# camera_interface.net
KiCad netlist of a schematic drawn in Altium Designer
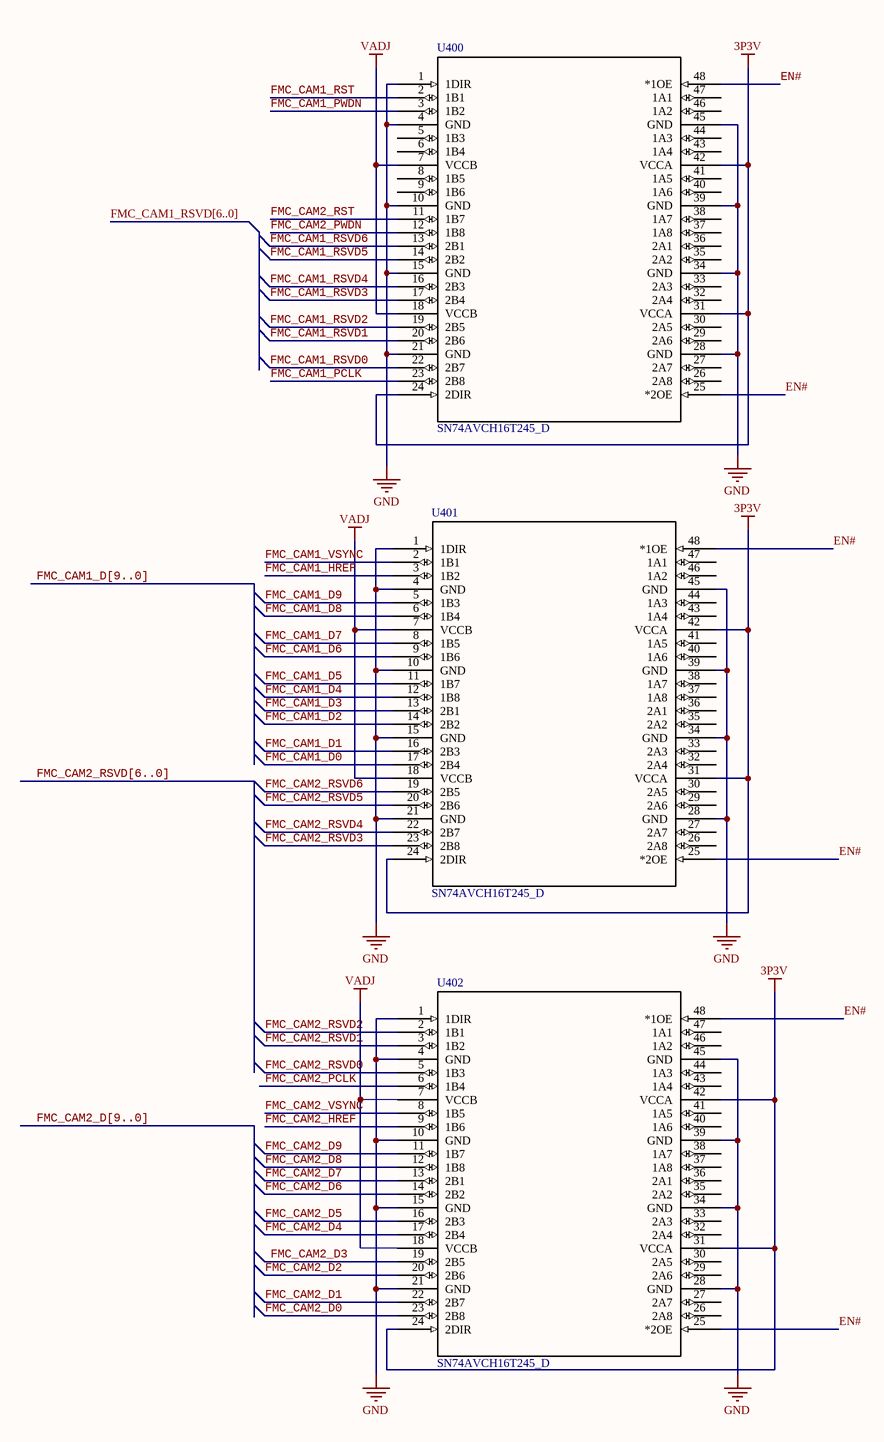
[diagram p0: camera_interface.SchDoc]

(export (version "E")
  (design (tool "Eeschema 10.0.6"))
  (components
    (comp (ref "U400")
      (value "SN74AVCH16T245_D")
      (footprint "DGV48")
      (description "Imported")
      (fields
        (field (name "MANUFACTURER") "Texas Instruments")
        (field (name "GENERIC_PART_NUMBER") "SN74AVCH16T245")
      )
      (libsource (lib "SN74AVCH16T245DGV") (part "SN74AVCH16T245_D"))
    )
    (comp (ref "U401")
      (value "SN74AVCH16T245_D")
      (footprint "DGV48")
      (description "Imported")
      (fields
        (field (name "MANUFACTURER") "Texas Instruments")
        (field (name "GENERIC_PART_NUMBER") "SN74AVCH16T245")
      )
      (libsource (lib "SN74AVCH16T245DGV") (part "SN74AVCH16T245_D"))
    )
    (comp (ref "U402")
      (value "SN74AVCH16T245_D")
      (footprint "DGV48")
      (description "Imported")
      (fields
        (field (name "MANUFACTURER") "Texas Instruments")
        (field (name "GENERIC_PART_NUMBER") "SN74AVCH16T245")
      )
      (libsource (lib "SN74AVCH16T245DGV") (part "SN74AVCH16T245_D"))
    )
  )
  (nets
    (net (code "1") (name "/EN#") (class "Default")
      (node (ref "U400") (pin "25") (pinfunction "*2OE_25") (pintype "input"))
      (node (ref "U400") (pin "48") (pinfunction "*1OE_48") (pintype "input"))
      (node (ref "U401") (pin "25") (pinfunction "*2OE_25") (pintype "input"))
      (node (ref "U401") (pin "48") (pinfunction "*1OE_48") (pintype "input"))
      (node (ref "U402") (pin "25") (pinfunction "*2OE_25") (pintype "input"))
      (node (ref "U402") (pin "48") (pinfunction "*1OE_48") (pintype "input"))
    )
    (net (code "2") (name "/FMC_CAM1_D0") (class "Default")
      (node (ref "U401") (pin "17") (pinfunction "2B4_17") (pintype "bidirectional"))
    )
    (net (code "3") (name "/FMC_CAM1_D1") (class "Default")
      (node (ref "U401") (pin "16") (pinfunction "2B3_16") (pintype "bidirectional"))
    )
    (net (code "4") (name "/FMC_CAM1_D2") (class "Default")
      (node (ref "U401") (pin "14") (pinfunction "2B2_14") (pintype "bidirectional"))
    )
    (net (code "5") (name "/FMC_CAM1_D3") (class "Default")
      (node (ref "U401") (pin "13") (pinfunction "2B1_13") (pintype "bidirectional"))
    )
    (net (code "6") (name "/FMC_CAM1_D4") (class "Default")
      (node (ref "U401") (pin "12") (pinfunction "1B8_12") (pintype "bidirectional"))
    )
    (net (code "7") (name "/FMC_CAM1_D5") (class "Default")
      (node (ref "U401") (pin "11") (pinfunction "1B7_11") (pintype "bidirectional"))
    )
    (net (code "8") (name "/FMC_CAM1_D6") (class "Default")
      (node (ref "U401") (pin "9") (pinfunction "1B6_9") (pintype "bidirectional"))
    )
    (net (code "9") (name "/FMC_CAM1_D7") (class "Default")
      (node (ref "U401") (pin "8") (pinfunction "1B5_8") (pintype "bidirectional"))
    )
    (net (code "10") (name "/FMC_CAM1_D8") (class "Default")
      (node (ref "U401") (pin "6") (pinfunction "1B4_6") (pintype "bidirectional"))
    )
    (net (code "11") (name "/FMC_CAM1_D9") (class "Default")
      (node (ref "U401") (pin "5") (pinfunction "1B3_5") (pintype "bidirectional"))
    )
    (net (code "13") (name "/FMC_CAM1_HREF") (class "Default")
      (node (ref "U401") (pin "3") (pinfunction "1B2_3") (pintype "bidirectional"))
    )
    (net (code "14") (name "/FMC_CAM1_PCLK") (class "Default")
      (node (ref "U400") (pin "23") (pinfunction "2B8_23") (pintype "bidirectional"))
    )
    (net (code "15") (name "/FMC_CAM1_PWDN") (class "Default")
      (node (ref "U400") (pin "3") (pinfunction "1B2_3") (pintype "bidirectional"))
    )
    (net (code "16") (name "/FMC_CAM1_RST") (class "Default")
      (node (ref "U400") (pin "2") (pinfunction "1B1_2") (pintype "bidirectional"))
    )
    (net (code "17") (name "/FMC_CAM1_RSVD0") (class "Default")
      (node (ref "U400") (pin "22") (pinfunction "2B7_22") (pintype "bidirectional"))
    )
    (net (code "18") (name "/FMC_CAM1_RSVD1") (class "Default")
      (node (ref "U400") (pin "20") (pinfunction "2B6_20") (pintype "bidirectional"))
    )
    (net (code "19") (name "/FMC_CAM1_RSVD2") (class "Default")
      (node (ref "U400") (pin "19") (pinfunction "2B5_19") (pintype "bidirectional"))
    )
    (net (code "20") (name "/FMC_CAM1_RSVD3") (class "Default")
      (node (ref "U400") (pin "17") (pinfunction "2B4_17") (pintype "bidirectional"))
    )
    (net (code "21") (name "/FMC_CAM1_RSVD4") (class "Default")
      (node (ref "U400") (pin "16") (pinfunction "2B3_16") (pintype "bidirectional"))
    )
    (net (code "22") (name "/FMC_CAM1_RSVD5") (class "Default")
      (node (ref "U400") (pin "14") (pinfunction "2B2_14") (pintype "bidirectional"))
    )
    (net (code "23") (name "/FMC_CAM1_RSVD6") (class "Default")
      (node (ref "U400") (pin "13") (pinfunction "2B1_13") (pintype "bidirectional"))
    )
    (net (code "25") (name "/FMC_CAM1_VSYNC") (class "Default")
      (node (ref "U401") (pin "2") (pinfunction "1B1_2") (pintype "bidirectional"))
    )
    (net (code "26") (name "/FMC_CAM2_D0") (class "Default")
      (node (ref "U402") (pin "23") (pinfunction "2B8_23") (pintype "bidirectional"))
    )
    (net (code "27") (name "/FMC_CAM2_D1") (class "Default")
      (node (ref "U402") (pin "22") (pinfunction "2B7_22") (pintype "bidirectional"))
    )
    (net (code "28") (name "/FMC_CAM2_D2") (class "Default")
      (node (ref "U402") (pin "20") (pinfunction "2B6_20") (pintype "bidirectional"))
    )
    (net (code "29") (name "/FMC_CAM2_D3") (class "Default")
      (node (ref "U402") (pin "19") (pinfunction "2B5_19") (pintype "bidirectional"))
    )
    (net (code "30") (name "/FMC_CAM2_D4") (class "Default")
      (node (ref "U402") (pin "17") (pinfunction "2B4_17") (pintype "bidirectional"))
    )
    (net (code "31") (name "/FMC_CAM2_D5") (class "Default")
      (node (ref "U402") (pin "16") (pinfunction "2B3_16") (pintype "bidirectional"))
    )
    (net (code "32") (name "/FMC_CAM2_D6") (class "Default")
      (node (ref "U402") (pin "14") (pinfunction "2B2_14") (pintype "bidirectional"))
    )
    (net (code "33") (name "/FMC_CAM2_D7") (class "Default")
      (node (ref "U402") (pin "13") (pinfunction "2B1_13") (pintype "bidirectional"))
    )
    (net (code "34") (name "/FMC_CAM2_D8") (class "Default")
      (node (ref "U402") (pin "12") (pinfunction "1B8_12") (pintype "bidirectional"))
    )
    (net (code "35") (name "/FMC_CAM2_D9") (class "Default")
      (node (ref "U402") (pin "11") (pinfunction "1B7_11") (pintype "bidirectional"))
    )
    (net (code "37") (name "/FMC_CAM2_HREF") (class "Default")
      (node (ref "U402") (pin "9") (pinfunction "1B6_9") (pintype "bidirectional"))
    )
    (net (code "38") (name "/FMC_CAM2_PCLK") (class "Default")
      (node (ref "U402") (pin "6") (pinfunction "1B4_6") (pintype "bidirectional"))
    )
    (net (code "39") (name "/FMC_CAM2_PWDN") (class "Default")
      (node (ref "U400") (pin "12") (pinfunction "1B8_12") (pintype "bidirectional"))
    )
    (net (code "40") (name "/FMC_CAM2_RST") (class "Default")
      (node (ref "U400") (pin "11") (pinfunction "1B7_11") (pintype "bidirectional"))
    )
    (net (code "41") (name "/FMC_CAM2_RSVD0") (class "Default")
      (node (ref "U402") (pin "5") (pinfunction "1B3_5") (pintype "bidirectional"))
    )
    (net (code "42") (name "/FMC_CAM2_RSVD1") (class "Default")
      (node (ref "U402") (pin "3") (pinfunction "1B2_3") (pintype "bidirectional"))
    )
    (net (code "43") (name "/FMC_CAM2_RSVD2") (class "Default")
      (node (ref "U402") (pin "2") (pinfunction "1B1_2") (pintype "bidirectional"))
    )
    (net (code "44") (name "/FMC_CAM2_RSVD3") (class "Default")
      (node (ref "U401") (pin "23") (pinfunction "2B8_23") (pintype "bidirectional"))
    )
    (net (code "45") (name "/FMC_CAM2_RSVD4") (class "Default")
      (node (ref "U401") (pin "22") (pinfunction "2B7_22") (pintype "bidirectional"))
    )
    (net (code "46") (name "/FMC_CAM2_RSVD5") (class "Default")
      (node (ref "U401") (pin "20") (pinfunction "2B6_20") (pintype "bidirectional"))
    )
    (net (code "47") (name "/FMC_CAM2_RSVD6") (class "Default")
      (node (ref "U401") (pin "19") (pinfunction "2B5_19") (pintype "bidirectional"))
    )
    (net (code "49") (name "/FMC_CAM2_VSYNC") (class "Default")
      (node (ref "U402") (pin "8") (pinfunction "1B5_8") (pintype "bidirectional"))
    )
    (net (code "50") (name "3P3V") (class "Default")
      (node (ref "U400") (pin "24") (pinfunction "2DIR_24") (pintype "input"))
      (node (ref "U400") (pin "31") (pinfunction "VCCA_31") (pintype "power_in"))
      (node (ref "U400") (pin "42") (pinfunction "VCCA_42") (pintype "power_in"))
      (node (ref "U401") (pin "24") (pinfunction "2DIR_24") (pintype "input"))
      (node (ref "U401") (pin "31") (pinfunction "VCCA_31") (pintype "power_in"))
      (node (ref "U401") (pin "42") (pinfunction "VCCA_42") (pintype "power_in"))
      (node (ref "U402") (pin "24") (pinfunction "2DIR_24") (pintype "input"))
      (node (ref "U402") (pin "31") (pinfunction "VCCA_31") (pintype "power_in"))
      (node (ref "U402") (pin "42") (pinfunction "VCCA_42") (pintype "power_in"))
    )
    (net (code "51") (name "GND") (class "Default")
      (node (ref "U400") (pin "1") (pinfunction "1DIR_1") (pintype "input"))
      (node (ref "U400") (pin "10") (pinfunction "GND_10") (pintype "power_in"))
      (node (ref "U400") (pin "15") (pinfunction "GND_15") (pintype "power_in"))
      (node (ref "U400") (pin "21") (pinfunction "GND_21") (pintype "power_in"))
      (node (ref "U400") (pin "28") (pinfunction "GND_28") (pintype "power_in"))
      (node (ref "U400") (pin "34") (pinfunction "GND_34") (pintype "power_in"))
      (node (ref "U400") (pin "39") (pinfunction "GND_39") (pintype "power_in"))
      (node (ref "U400") (pin "4") (pinfunction "GND_4") (pintype "power_in"))
      (node (ref "U400") (pin "45") (pinfunction "GND_45") (pintype "power_in"))
      (node (ref "U401") (pin "1") (pinfunction "1DIR_1") (pintype "input"))
      (node (ref "U401") (pin "10") (pinfunction "GND_10") (pintype "power_in"))
      (node (ref "U401") (pin "15") (pinfunction "GND_15") (pintype "power_in"))
      (node (ref "U401") (pin "21") (pinfunction "GND_21") (pintype "power_in"))
      (node (ref "U401") (pin "28") (pinfunction "GND_28") (pintype "power_in"))
      (node (ref "U401") (pin "34") (pinfunction "GND_34") (pintype "power_in"))
      (node (ref "U401") (pin "39") (pinfunction "GND_39") (pintype "power_in"))
      (node (ref "U401") (pin "4") (pinfunction "GND_4") (pintype "power_in"))
      (node (ref "U401") (pin "45") (pinfunction "GND_45") (pintype "power_in"))
      (node (ref "U402") (pin "1") (pinfunction "1DIR_1") (pintype "input"))
      (node (ref "U402") (pin "10") (pinfunction "GND_10") (pintype "power_in"))
      (node (ref "U402") (pin "15") (pinfunction "GND_15") (pintype "power_in"))
      (node (ref "U402") (pin "21") (pinfunction "GND_21") (pintype "power_in"))
      (node (ref "U402") (pin "28") (pinfunction "GND_28") (pintype "power_in"))
      (node (ref "U402") (pin "34") (pinfunction "GND_34") (pintype "power_in"))
      (node (ref "U402") (pin "39") (pinfunction "GND_39") (pintype "power_in"))
      (node (ref "U402") (pin "4") (pinfunction "GND_4") (pintype "power_in"))
      (node (ref "U402") (pin "45") (pinfunction "GND_45") (pintype "power_in"))
    )
    (net (code "52") (name "VADJ") (class "Default")
      (node (ref "U400") (pin "18") (pinfunction "VCCB_18") (pintype "power_in"))
      (node (ref "U400") (pin "7") (pinfunction "VCCB_7") (pintype "power_in"))
      (node (ref "U401") (pin "18") (pinfunction "VCCB_18") (pintype "power_in"))
      (node (ref "U401") (pin "7") (pinfunction "VCCB_7") (pintype "power_in"))
      (node (ref "U402") (pin "18") (pinfunction "VCCB_18") (pintype "power_in"))
      (node (ref "U402") (pin "7") (pinfunction "VCCB_7") (pintype "power_in"))
    )
    (net (code "53") (name "unconnected-(U400-1A1-Pad47)") (class "Default")
      (node (ref "U400") (pin "47") (pinfunction "1A1_47") (pintype "bidirectional"))
    )
    (net (code "54") (name "unconnected-(U400-1A2-Pad46)") (class "Default")
      (node (ref "U400") (pin "46") (pinfunction "1A2_46") (pintype "bidirectional"))
    )
    (net (code "55") (name "unconnected-(U400-1A3-Pad44)") (class "Default")
      (node (ref "U400") (pin "44") (pinfunction "1A3_44") (pintype "bidirectional"))
    )
    (net (code "56") (name "unconnected-(U400-1A4-Pad43)") (class "Default")
      (node (ref "U400") (pin "43") (pinfunction "1A4_43") (pintype "bidirectional"))
    )
    (net (code "57") (name "unconnected-(U400-1A5-Pad41)") (class "Default")
      (node (ref "U400") (pin "41") (pinfunction "1A5_41") (pintype "bidirectional"))
    )
    (net (code "58") (name "unconnected-(U400-1A6-Pad40)") (class "Default")
      (node (ref "U400") (pin "40") (pinfunction "1A6_40") (pintype "bidirectional"))
    )
    (net (code "59") (name "unconnected-(U400-1A7-Pad38)") (class "Default")
      (node (ref "U400") (pin "38") (pinfunction "1A7_38") (pintype "bidirectional"))
    )
    (net (code "60") (name "unconnected-(U400-1A8-Pad37)") (class "Default")
      (node (ref "U400") (pin "37") (pinfunction "1A8_37") (pintype "bidirectional"))
    )
    (net (code "61") (name "unconnected-(U400-1B3-Pad5)") (class "Default")
      (node (ref "U400") (pin "5") (pinfunction "1B3_5") (pintype "bidirectional"))
    )
    (net (code "62") (name "unconnected-(U400-1B4-Pad6)") (class "Default")
      (node (ref "U400") (pin "6") (pinfunction "1B4_6") (pintype "bidirectional"))
    )
    (net (code "63") (name "unconnected-(U400-1B5-Pad8)") (class "Default")
      (node (ref "U400") (pin "8") (pinfunction "1B5_8") (pintype "bidirectional"))
    )
    (net (code "64") (name "unconnected-(U400-1B6-Pad9)") (class "Default")
      (node (ref "U400") (pin "9") (pinfunction "1B6_9") (pintype "bidirectional"))
    )
    (net (code "65") (name "unconnected-(U400-2A1-Pad36)") (class "Default")
      (node (ref "U400") (pin "36") (pinfunction "2A1_36") (pintype "bidirectional"))
    )
    (net (code "66") (name "unconnected-(U400-2A2-Pad35)") (class "Default")
      (node (ref "U400") (pin "35") (pinfunction "2A2_35") (pintype "bidirectional"))
    )
    (net (code "67") (name "unconnected-(U400-2A3-Pad33)") (class "Default")
      (node (ref "U400") (pin "33") (pinfunction "2A3_33") (pintype "bidirectional"))
    )
    (net (code "68") (name "unconnected-(U400-2A4-Pad32)") (class "Default")
      (node (ref "U400") (pin "32") (pinfunction "2A4_32") (pintype "bidirectional"))
    )
    (net (code "69") (name "unconnected-(U400-2A5-Pad30)") (class "Default")
      (node (ref "U400") (pin "30") (pinfunction "2A5_30") (pintype "bidirectional"))
    )
    (net (code "70") (name "unconnected-(U400-2A6-Pad29)") (class "Default")
      (node (ref "U400") (pin "29") (pinfunction "2A6_29") (pintype "bidirectional"))
    )
    (net (code "71") (name "unconnected-(U400-2A7-Pad27)") (class "Default")
      (node (ref "U400") (pin "27") (pinfunction "2A7_27") (pintype "bidirectional"))
    )
    (net (code "72") (name "unconnected-(U400-2A8-Pad26)") (class "Default")
      (node (ref "U400") (pin "26") (pinfunction "2A8_26") (pintype "bidirectional"))
    )
    (net (code "73") (name "unconnected-(U401-1A1-Pad47)") (class "Default")
      (node (ref "U401") (pin "47") (pinfunction "1A1_47") (pintype "bidirectional"))
    )
    (net (code "74") (name "unconnected-(U401-1A2-Pad46)") (class "Default")
      (node (ref "U401") (pin "46") (pinfunction "1A2_46") (pintype "bidirectional"))
    )
    (net (code "75") (name "unconnected-(U401-1A3-Pad44)") (class "Default")
      (node (ref "U401") (pin "44") (pinfunction "1A3_44") (pintype "bidirectional"))
    )
    (net (code "76") (name "unconnected-(U401-1A4-Pad43)") (class "Default")
      (node (ref "U401") (pin "43") (pinfunction "1A4_43") (pintype "bidirectional"))
    )
    (net (code "77") (name "unconnected-(U401-1A5-Pad41)") (class "Default")
      (node (ref "U401") (pin "41") (pinfunction "1A5_41") (pintype "bidirectional"))
    )
    (net (code "78") (name "unconnected-(U401-1A6-Pad40)") (class "Default")
      (node (ref "U401") (pin "40") (pinfunction "1A6_40") (pintype "bidirectional"))
    )
    (net (code "79") (name "unconnected-(U401-1A7-Pad38)") (class "Default")
      (node (ref "U401") (pin "38") (pinfunction "1A7_38") (pintype "bidirectional"))
    )
    (net (code "80") (name "unconnected-(U401-1A8-Pad37)") (class "Default")
      (node (ref "U401") (pin "37") (pinfunction "1A8_37") (pintype "bidirectional"))
    )
    (net (code "81") (name "unconnected-(U401-2A1-Pad36)") (class "Default")
      (node (ref "U401") (pin "36") (pinfunction "2A1_36") (pintype "bidirectional"))
    )
    (net (code "82") (name "unconnected-(U401-2A2-Pad35)") (class "Default")
      (node (ref "U401") (pin "35") (pinfunction "2A2_35") (pintype "bidirectional"))
    )
    (net (code "83") (name "unconnected-(U401-2A3-Pad33)") (class "Default")
      (node (ref "U401") (pin "33") (pinfunction "2A3_33") (pintype "bidirectional"))
    )
    (net (code "84") (name "unconnected-(U401-2A4-Pad32)") (class "Default")
      (node (ref "U401") (pin "32") (pinfunction "2A4_32") (pintype "bidirectional"))
    )
    (net (code "85") (name "unconnected-(U401-2A5-Pad30)") (class "Default")
      (node (ref "U401") (pin "30") (pinfunction "2A5_30") (pintype "bidirectional"))
    )
    (net (code "86") (name "unconnected-(U401-2A6-Pad29)") (class "Default")
      (node (ref "U401") (pin "29") (pinfunction "2A6_29") (pintype "bidirectional"))
    )
    (net (code "87") (name "unconnected-(U401-2A7-Pad27)") (class "Default")
      (node (ref "U401") (pin "27") (pinfunction "2A7_27") (pintype "bidirectional"))
    )
    (net (code "88") (name "unconnected-(U401-2A8-Pad26)") (class "Default")
      (node (ref "U401") (pin "26") (pinfunction "2A8_26") (pintype "bidirectional"))
    )
    (net (code "89") (name "unconnected-(U402-1A1-Pad47)") (class "Default")
      (node (ref "U402") (pin "47") (pinfunction "1A1_47") (pintype "bidirectional"))
    )
    (net (code "90") (name "unconnected-(U402-1A2-Pad46)") (class "Default")
      (node (ref "U402") (pin "46") (pinfunction "1A2_46") (pintype "bidirectional"))
    )
    (net (code "91") (name "unconnected-(U402-1A3-Pad44)") (class "Default")
      (node (ref "U402") (pin "44") (pinfunction "1A3_44") (pintype "bidirectional"))
    )
    (net (code "92") (name "unconnected-(U402-1A4-Pad43)") (class "Default")
      (node (ref "U402") (pin "43") (pinfunction "1A4_43") (pintype "bidirectional"))
    )
    (net (code "93") (name "unconnected-(U402-1A5-Pad41)") (class "Default")
      (node (ref "U402") (pin "41") (pinfunction "1A5_41") (pintype "bidirectional"))
    )
    (net (code "94") (name "unconnected-(U402-1A6-Pad40)") (class "Default")
      (node (ref "U402") (pin "40") (pinfunction "1A6_40") (pintype "bidirectional"))
    )
    (net (code "95") (name "unconnected-(U402-1A7-Pad38)") (class "Default")
      (node (ref "U402") (pin "38") (pinfunction "1A7_38") (pintype "bidirectional"))
    )
    (net (code "96") (name "unconnected-(U402-1A8-Pad37)") (class "Default")
      (node (ref "U402") (pin "37") (pinfunction "1A8_37") (pintype "bidirectional"))
    )
    (net (code "97") (name "unconnected-(U402-2A1-Pad36)") (class "Default")
      (node (ref "U402") (pin "36") (pinfunction "2A1_36") (pintype "bidirectional"))
    )
    (net (code "98") (name "unconnected-(U402-2A2-Pad35)") (class "Default")
      (node (ref "U402") (pin "35") (pinfunction "2A2_35") (pintype "bidirectional"))
    )
    (net (code "99") (name "unconnected-(U402-2A3-Pad33)") (class "Default")
      (node (ref "U402") (pin "33") (pinfunction "2A3_33") (pintype "bidirectional"))
    )
    (net (code "100") (name "unconnected-(U402-2A4-Pad32)") (class "Default")
      (node (ref "U402") (pin "32") (pinfunction "2A4_32") (pintype "bidirectional"))
    )
    (net (code "101") (name "unconnected-(U402-2A5-Pad30)") (class "Default")
      (node (ref "U402") (pin "30") (pinfunction "2A5_30") (pintype "bidirectional"))
    )
    (net (code "102") (name "unconnected-(U402-2A6-Pad29)") (class "Default")
      (node (ref "U402") (pin "29") (pinfunction "2A6_29") (pintype "bidirectional"))
    )
    (net (code "103") (name "unconnected-(U402-2A7-Pad27)") (class "Default")
      (node (ref "U402") (pin "27") (pinfunction "2A7_27") (pintype "bidirectional"))
    )
    (net (code "104") (name "unconnected-(U402-2A8-Pad26)") (class "Default")
      (node (ref "U402") (pin "26") (pinfunction "2A8_26") (pintype "bidirectional"))
    )
  )
)
